# MSE450_G05_ASTEROIDS.net
KiCad netlist of a schematic drawn in Altium Designer
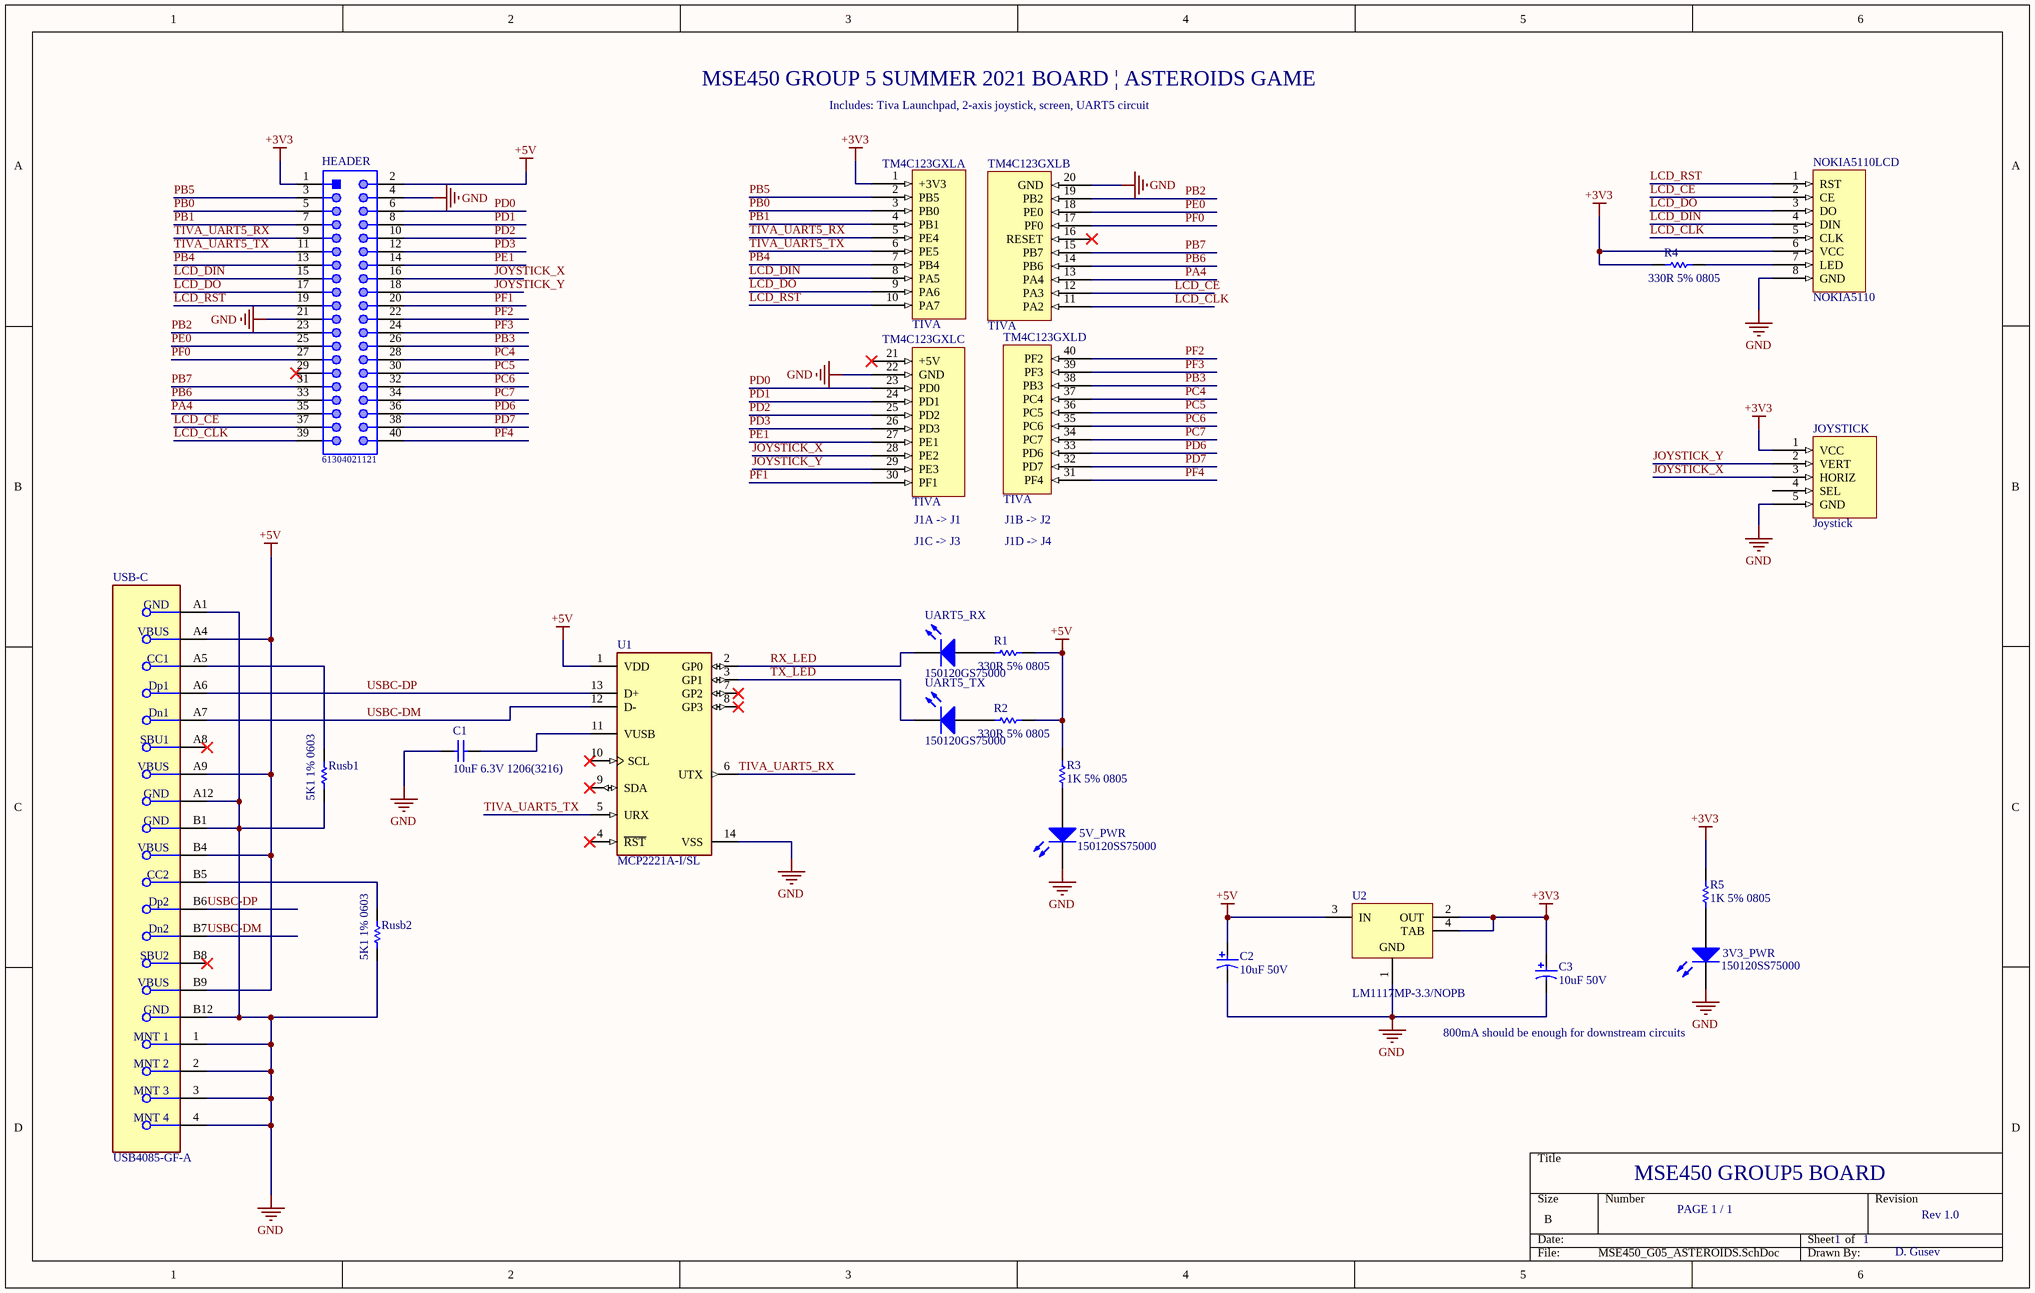
[diagram p0: MSE450_G05_ASTEROIDS.SchDoc]

(export (version "E")
  (design (tool "Eeschema 10.0.6"))
  (components
    (comp (ref "3V3_PWR")
      (value "150120SS75000")
      (footprint "1206_A")
      (description "SMD mono-color Chip LED, WL-SMCW, Super Red")
      (fields (field (name "MANUFACTURER") "Wuerth Elektronik"))
      (libsource (lib "Altium Content Vault") (part "WE-LED_K1A2-2"))
    )
    (comp (ref "5V_PWR")
      (value "150120SS75000")
      (footprint "1206_A")
      (description "SMD mono-color Chip LED, WL-SMCW, Super Red")
      (fields (field (name "MANUFACTURER") "Wuerth Elektronik"))
      (libsource (lib "Altium Content Vault") (part "WE-LED_K1A2-2"))
    )
    (comp (ref "C1")
      (value "10uF 6.3V 1206(3216)")
      (footprint "CAPC1206(3216)190_N")
      (description "CAP 10uF 6.3V ±10% 1206 (3216 Metric) Thickness 1.9mm SMD")
      (fields (field (name "TOLERANCE") "Â±10%"))
      (libsource (lib "Altium Content Vault") (part "CAP"))
    )
    (comp (ref "C2")
      (value "10uF 50V")
      (footprint "PNSC-FK-V-D_V")
      (fields (field (name "MANUFACTURER") "Panasonic"))
      (libsource (lib "Altium Content Vault") (part "CAP-P-2"))
    )
    (comp (ref "C3")
      (value "10uF 50V")
      (footprint "PNSC-FK-V-D_V")
      (fields (field (name "MANUFACTURER") "Panasonic"))
      (libsource (lib "Altium Content Vault") (part "CAP-P-2"))
    )
    (comp (ref "HEADER")
      (value "61304021121")
      (footprint "61304021121")
      (description "THT Vertical Pin Header WR-PHD, Pitch 2.54 mm, Dual Row, 40 pins")
      (fields (field (name "MANUFACTURER") "Wurth Elektronik") (field (name "PUBLISHER") "WurthElektronik"))
      (libsource (lib "Altium Content Vault") (part "WE-CN-2P-M-R40"))
    )
    (comp (ref "JOYSTICK")
      (value "Joystick")
      (footprint "joystick")
      (libsource (lib "MSE450_G05_ASTEROIDS") (part "Joystick"))
    )
    (comp (ref "NOKIA5110LCD")
      (value "NOKIA5110")
      (footprint "NOKIA5110")
      (libsource (lib "MSE450_G05_ASTEROIDS") (part "NOKIA5110"))
    )
    (comp (ref "R1")
      (value "330R 5% 0805")
      (footprint "RESC2013X60X40ML20T25")
      (fields (field (name "PART NUMBER") "ERA6AEB123V") (field (name "MANUFACTURER") "Panasonic"))
      (libsource (lib "Altium Content Vault") (part "RES"))
    )
    (comp (ref "R2")
      (value "330R 5% 0805")
      (footprint "RESC2013X60X40ML20T25")
      (fields (field (name "PART NUMBER") "ERA6AEB123V") (field (name "MANUFACTURER") "Panasonic"))
      (libsource (lib "Altium Content Vault") (part "RES"))
    )
    (comp (ref "R3")
      (value "1K 5% 0805")
      (footprint "RESC2013X60X40ML20T25")
      (fields (field (name "PART NUMBER") "ERA6AEB123V") (field (name "MANUFACTURER") "Panasonic"))
      (libsource (lib "Altium Content Vault") (part "RES"))
    )
    (comp (ref "R4")
      (value "330R 5% 0805")
      (footprint "RESC2013X60X40ML20T25")
      (fields (field (name "PART NUMBER") "ERA6AEB123V") (field (name "MANUFACTURER") "Panasonic"))
      (libsource (lib "Altium Content Vault") (part "RES"))
    )
    (comp (ref "R5")
      (value "1K 5% 0805")
      (footprint "RESC2013X60X40ML20T25")
      (fields (field (name "PART NUMBER") "ERA6AEB123V") (field (name "MANUFACTURER") "Panasonic"))
      (libsource (lib "Altium Content Vault") (part "RES"))
    )
    (comp (ref "Rusb1")
      (value "5K1 1% 0603")
      (footprint "RESC1608X55X25ML10T15")
      (fields (field (name "MANUFACTURER") "Yageo") (field (name "PART NUMBER") "RC0603FR-075K1L"))
      (libsource (lib "Altium Content Vault") (part "RES"))
    )
    (comp (ref "Rusb2")
      (value "5K1 1% 0603")
      (footprint "RESC1608X55X25ML10T15")
      (fields (field (name "MANUFACTURER") "Yageo") (field (name "PART NUMBER") "RC0603FR-075K1L"))
      (libsource (lib "Altium Content Vault") (part "RES"))
    )
    (comp (ref "TM4C123GXL")
      (value "TIVA")
      (footprint "TIVA")
      (libsource (lib "MSE450_G05_ASTEROIDS") (part "TIVA"))
    )
    (comp (ref "U1")
      (value "MCP2221A-I/SL")
      (footprint "FP-C04-065-SL-MFG")
      (description "IC USB TO I2C/UART 14SOIC")
      (fields
        (field (name "OCTOPART") "https://octopart.com/mcp2221a-i%2Fsl-microchip-71704986")
        (field (name "MANUFACTURER") "Microchip")
      )
      (libsource (lib "Altium Content Vault") (part "1b53208594fde27bd45fc2fa1d78706"))
    )
    (comp (ref "U2")
      (value "LM1117MP-3.3/NOPB")
      (footprint "DCY0004A_L")
      (description "800mA Low-Dropout Linear Regulator, 4-pin SOT-223, Pb-Free")
      (fields (field (name "MANUFACTURER") "Texas Instruments"))
      (libsource (lib "Altium Content Vault") (part "PM-REG-LM1086-SOT4"))
    )
    (comp (ref "UART5_RX")
      (value "150120GS75000")
      (footprint "1206_A")
      (description "SMD mono-color Chip LED, WL-SMCW, Green")
      (fields (field (name "MANUFACTURER") "Wuerth Elektronik"))
      (libsource (lib "Altium Content Vault") (part "WE-LED_K1A2-2"))
    )
    (comp (ref "UART5_TX")
      (value "150120GS75000")
      (footprint "1206_A")
      (description "SMD mono-color Chip LED, WL-SMCW, Green")
      (fields (field (name "MANUFACTURER") "Wuerth Elektronik"))
      (libsource (lib "Altium Content Vault") (part "WE-LED_K1A2-2"))
    )
    (comp (ref "USB-C")
      (value "USB4085-GF-A")
      (footprint "FP-USB4085-GF-A-MFG")
      (description "CONN RCPT USB2.0 TYPEC 16POS")
      (fields
        (field (name "MANUFACTURER") "Global Connector Technology")
        (field (name "OCTOPART") "https://octopart.com/usb4085-gf-a-global+connector+technology-94773699")
      )
      (libsource (lib "Altium Content Vault") (part "f6997dba88850a18107ac0013977506"))
    )
  )
  (nets
    (net (code "1") (name "+3V3") (class "Default")
      (node (ref "C3") (pin "1") (pinfunction "1_1") (pintype "passive"))
      (node (ref "HEADER") (pin "1") (pinfunction "1_1") (pintype "passive"))
      (node (ref "JOYSTICK") (pin "1") (pinfunction "VCC_1") (pintype "input"))
      (node (ref "NOKIA5110LCD") (pin "6") (pinfunction "VCC_6") (pintype "input"))
      (node (ref "R4") (pin "2") (pinfunction "2_2") (pintype "passive"))
      (node (ref "R5") (pin "1") (pinfunction "1_1") (pintype "passive"))
      (node (ref "TM4C123GXL") (pin "1") (pinfunction "+3V3_1") (pintype "input"))
      (node (ref "U2") (pin "2") (pinfunction "OUT_2") (pintype "power_in"))
      (node (ref "U2") (pin "4") (pinfunction "TAB_4") (pintype "power_in"))
    )
    (net (code "2") (name "+5V") (class "Default")
      (node (ref "C2") (pin "1") (pinfunction "1_1") (pintype "passive"))
      (node (ref "HEADER") (pin "2") (pinfunction "2_2") (pintype "passive"))
      (node (ref "R1") (pin "1") (pinfunction "1_1") (pintype "passive"))
      (node (ref "R2") (pin "1") (pinfunction "1_1") (pintype "passive"))
      (node (ref "R3") (pin "1") (pinfunction "1_1") (pintype "passive"))
      (node (ref "U1") (pin "1") (pinfunction "VDD_1") (pintype "power_in"))
      (node (ref "U2") (pin "3") (pinfunction "IN_3") (pintype "power_in"))
      (node (ref "USB-C") (pin "A4") (pinfunction "VBUS_A4") (pintype "power_in"))
      (node (ref "USB-C") (pin "A9") (pinfunction "VBUS_A9") (pintype "power_in"))
      (node (ref "USB-C") (pin "B4") (pinfunction "VBUS_B4") (pintype "power_in"))
      (node (ref "USB-C") (pin "B9") (pinfunction "VBUS_B9") (pintype "power_in"))
    )
    (net (code "3") (name "/JOYSTICK_X") (class "Default")
      (node (ref "HEADER") (pin "16") (pinfunction "16_16") (pintype "passive"))
      (node (ref "JOYSTICK") (pin "3") (pinfunction "HORIZ_3") (pintype "input"))
      (node (ref "TM4C123GXL") (pin "28") (pinfunction "PE2_28") (pintype "input"))
    )
    (net (code "4") (name "/JOYSTICK_Y") (class "Default")
      (node (ref "HEADER") (pin "18") (pinfunction "18_18") (pintype "passive"))
      (node (ref "JOYSTICK") (pin "2") (pinfunction "VERT_2") (pintype "input"))
      (node (ref "TM4C123GXL") (pin "29") (pinfunction "PE3_29") (pintype "input"))
    )
    (net (code "5") (name "/LCD_CE") (class "Default")
      (node (ref "HEADER") (pin "37") (pinfunction "37_37") (pintype "passive"))
      (node (ref "NOKIA5110LCD") (pin "2") (pinfunction "CE_2") (pintype "input"))
      (node (ref "TM4C123GXL") (pin "12") (pinfunction "PA3_12") (pintype "input"))
    )
    (net (code "6") (name "/LCD_CLK") (class "Default")
      (node (ref "HEADER") (pin "39") (pinfunction "39_39") (pintype "passive"))
      (node (ref "NOKIA5110LCD") (pin "5") (pinfunction "CLK_5") (pintype "input"))
      (node (ref "TM4C123GXL") (pin "11") (pinfunction "PA2_11") (pintype "input"))
    )
    (net (code "7") (name "/LCD_DIN") (class "Default")
      (node (ref "HEADER") (pin "15") (pinfunction "15_15") (pintype "passive"))
      (node (ref "NOKIA5110LCD") (pin "4") (pinfunction "DIN_4") (pintype "input"))
      (node (ref "TM4C123GXL") (pin "8") (pinfunction "PA5_8") (pintype "input"))
    )
    (net (code "8") (name "/LCD_DO") (class "Default")
      (node (ref "HEADER") (pin "17") (pinfunction "17_17") (pintype "passive"))
      (node (ref "NOKIA5110LCD") (pin "3") (pinfunction "DO_3") (pintype "input"))
      (node (ref "TM4C123GXL") (pin "9") (pinfunction "PA6_9") (pintype "input"))
    )
    (net (code "9") (name "/LCD_RST") (class "Default")
      (node (ref "HEADER") (pin "19") (pinfunction "19_19") (pintype "passive"))
      (node (ref "NOKIA5110LCD") (pin "1") (pinfunction "RST_1") (pintype "input"))
      (node (ref "TM4C123GXL") (pin "10") (pinfunction "PA7_10") (pintype "input"))
    )
    (net (code "10") (name "/PA4") (class "Default")
      (node (ref "HEADER") (pin "35") (pinfunction "35_35") (pintype "passive"))
      (node (ref "TM4C123GXL") (pin "13") (pinfunction "PA4_13") (pintype "input"))
    )
    (net (code "11") (name "/PB0") (class "Default")
      (node (ref "HEADER") (pin "5") (pinfunction "5_5") (pintype "passive"))
      (node (ref "TM4C123GXL") (pin "3") (pinfunction "PB0_3") (pintype "input"))
    )
    (net (code "12") (name "/PB1") (class "Default")
      (node (ref "HEADER") (pin "7") (pinfunction "7_7") (pintype "passive"))
      (node (ref "TM4C123GXL") (pin "4") (pinfunction "PB1_4") (pintype "input"))
    )
    (net (code "13") (name "/PB2") (class "Default")
      (node (ref "HEADER") (pin "23") (pinfunction "23_23") (pintype "passive"))
      (node (ref "TM4C123GXL") (pin "19") (pinfunction "PB2_19") (pintype "input"))
    )
    (net (code "14") (name "/PB3") (class "Default")
      (node (ref "HEADER") (pin "26") (pinfunction "26_26") (pintype "passive"))
      (node (ref "TM4C123GXL") (pin "38") (pinfunction "PB3_38") (pintype "input"))
    )
    (net (code "15") (name "/PB4") (class "Default")
      (node (ref "HEADER") (pin "13") (pinfunction "13_13") (pintype "passive"))
      (node (ref "TM4C123GXL") (pin "7") (pinfunction "PB4_7") (pintype "input"))
    )
    (net (code "16") (name "/PB5") (class "Default")
      (node (ref "HEADER") (pin "3") (pinfunction "3_3") (pintype "passive"))
      (node (ref "TM4C123GXL") (pin "2") (pinfunction "PB5_2") (pintype "input"))
    )
    (net (code "17") (name "/PB6") (class "Default")
      (node (ref "HEADER") (pin "33") (pinfunction "33_33") (pintype "passive"))
      (node (ref "TM4C123GXL") (pin "14") (pinfunction "PB6_14") (pintype "input"))
    )
    (net (code "18") (name "/PB7") (class "Default")
      (node (ref "HEADER") (pin "31") (pinfunction "31_31") (pintype "passive"))
      (node (ref "TM4C123GXL") (pin "15") (pinfunction "PB7_15") (pintype "input"))
    )
    (net (code "19") (name "/PC4") (class "Default")
      (node (ref "HEADER") (pin "28") (pinfunction "28_28") (pintype "passive"))
      (node (ref "TM4C123GXL") (pin "37") (pinfunction "PC4_37") (pintype "input"))
    )
    (net (code "20") (name "/PC5") (class "Default")
      (node (ref "HEADER") (pin "30") (pinfunction "30_30") (pintype "passive"))
      (node (ref "TM4C123GXL") (pin "36") (pinfunction "PC5_36") (pintype "input"))
    )
    (net (code "21") (name "/PC6") (class "Default")
      (node (ref "HEADER") (pin "32") (pinfunction "32_32") (pintype "passive"))
      (node (ref "TM4C123GXL") (pin "35") (pinfunction "PC6_35") (pintype "input"))
    )
    (net (code "22") (name "/PC7") (class "Default")
      (node (ref "HEADER") (pin "34") (pinfunction "34_34") (pintype "passive"))
      (node (ref "TM4C123GXL") (pin "34") (pinfunction "PC7_34") (pintype "input"))
    )
    (net (code "23") (name "/PD0") (class "Default")
      (node (ref "HEADER") (pin "6") (pinfunction "6_6") (pintype "passive"))
      (node (ref "TM4C123GXL") (pin "23") (pinfunction "PD0_23") (pintype "input"))
    )
    (net (code "24") (name "/PD1") (class "Default")
      (node (ref "HEADER") (pin "8") (pinfunction "8_8") (pintype "passive"))
      (node (ref "TM4C123GXL") (pin "24") (pinfunction "PD1_24") (pintype "input"))
    )
    (net (code "25") (name "/PD2") (class "Default")
      (node (ref "HEADER") (pin "10") (pinfunction "10_10") (pintype "passive"))
      (node (ref "TM4C123GXL") (pin "25") (pinfunction "PD2_25") (pintype "input"))
    )
    (net (code "26") (name "/PD3") (class "Default")
      (node (ref "HEADER") (pin "12") (pinfunction "12_12") (pintype "passive"))
      (node (ref "TM4C123GXL") (pin "26") (pinfunction "PD3_26") (pintype "input"))
    )
    (net (code "27") (name "/PD6") (class "Default")
      (node (ref "HEADER") (pin "36") (pinfunction "36_36") (pintype "passive"))
      (node (ref "TM4C123GXL") (pin "33") (pinfunction "PD6_33") (pintype "input"))
    )
    (net (code "28") (name "/PD7") (class "Default")
      (node (ref "HEADER") (pin "38") (pinfunction "38_38") (pintype "passive"))
      (node (ref "TM4C123GXL") (pin "32") (pinfunction "PD7_32") (pintype "input"))
    )
    (net (code "29") (name "/PE0") (class "Default")
      (node (ref "HEADER") (pin "25") (pinfunction "25_25") (pintype "passive"))
      (node (ref "TM4C123GXL") (pin "18") (pinfunction "PE0_18") (pintype "input"))
    )
    (net (code "30") (name "/PE1") (class "Default")
      (node (ref "HEADER") (pin "14") (pinfunction "14_14") (pintype "passive"))
      (node (ref "TM4C123GXL") (pin "27") (pinfunction "PE1_27") (pintype "input"))
    )
    (net (code "31") (name "/PF0") (class "Default")
      (node (ref "HEADER") (pin "27") (pinfunction "27_27") (pintype "passive"))
      (node (ref "TM4C123GXL") (pin "17") (pinfunction "PF0_17") (pintype "input"))
    )
    (net (code "32") (name "/PF1") (class "Default")
      (node (ref "HEADER") (pin "20") (pinfunction "20_20") (pintype "passive"))
      (node (ref "TM4C123GXL") (pin "30") (pinfunction "PF1_30") (pintype "input"))
    )
    (net (code "33") (name "/PF2") (class "Default")
      (node (ref "HEADER") (pin "22") (pinfunction "22_22") (pintype "passive"))
      (node (ref "TM4C123GXL") (pin "40") (pinfunction "PF2_40") (pintype "input"))
    )
    (net (code "34") (name "/PF3") (class "Default")
      (node (ref "HEADER") (pin "24") (pinfunction "24_24") (pintype "passive"))
      (node (ref "TM4C123GXL") (pin "39") (pinfunction "PF3_39") (pintype "input"))
    )
    (net (code "35") (name "/PF4") (class "Default")
      (node (ref "HEADER") (pin "40") (pinfunction "40_40") (pintype "passive"))
      (node (ref "TM4C123GXL") (pin "31") (pinfunction "PF4_31") (pintype "input"))
    )
    (net (code "36") (name "/RX_LED") (class "Default")
      (node (ref "U1") (pin "2") (pinfunction "GP0_2") (pintype "bidirectional"))
      (node (ref "UART5_RX") (pin "1") (pinfunction "K_1") (pintype "passive"))
    )
    (net (code "37") (name "/TIVA_UART5_RX") (class "Default")
      (node (ref "HEADER") (pin "9") (pinfunction "9_9") (pintype "passive"))
      (node (ref "TM4C123GXL") (pin "5") (pinfunction "PE4_5") (pintype "input"))
      (node (ref "U1") (pin "6") (pinfunction "UTX_6") (pintype "output"))
    )
    (net (code "38") (name "/TIVA_UART5_TX") (class "Default")
      (node (ref "HEADER") (pin "11") (pinfunction "11_11") (pintype "passive"))
      (node (ref "TM4C123GXL") (pin "6") (pinfunction "PE5_6") (pintype "input"))
      (node (ref "U1") (pin "5") (pinfunction "URX_5") (pintype "input"))
    )
    (net (code "39") (name "/TX_LED") (class "Default")
      (node (ref "U1") (pin "3") (pinfunction "GP1_3") (pintype "bidirectional"))
      (node (ref "UART5_TX") (pin "1") (pinfunction "K_1") (pintype "passive"))
    )
    (net (code "40") (name "/USBC-DM") (class "Default")
      (node (ref "U1") (pin "12") (pinfunction "D-_12") (pintype "power_in"))
      (node (ref "USB-C") (pin "A7") (pinfunction "Dn1_A7") (pintype "passive"))
      (node (ref "USB-C") (pin "B7") (pinfunction "Dn2_B7") (pintype "passive"))
    )
    (net (code "41") (name "/USBC-DP") (class "Default")
      (node (ref "U1") (pin "13") (pinfunction "D+_13") (pintype "power_in"))
      (node (ref "USB-C") (pin "A6") (pinfunction "Dp1_A6") (pintype "passive"))
      (node (ref "USB-C") (pin "B6") (pinfunction "Dp2_B6") (pintype "passive"))
    )
    (net (code "42") (name "GND") (class "Default")
      (node (ref "3V3_PWR") (pin "1") (pinfunction "K_1") (pintype "passive"))
      (node (ref "5V_PWR") (pin "1") (pinfunction "K_1") (pintype "passive"))
      (node (ref "C1") (pin "1") (pinfunction "1_1") (pintype "passive"))
      (node (ref "C2") (pin "2") (pinfunction "2_2") (pintype "passive"))
      (node (ref "C3") (pin "2") (pinfunction "2_2") (pintype "passive"))
      (node (ref "HEADER") (pin "21") (pinfunction "21_21") (pintype "passive"))
      (node (ref "HEADER") (pin "4") (pinfunction "4_4") (pintype "passive"))
      (node (ref "JOYSTICK") (pin "5") (pinfunction "GND_5") (pintype "input"))
      (node (ref "NOKIA5110LCD") (pin "8") (pinfunction "GND_8") (pintype "input"))
      (node (ref "Rusb1") (pin "1") (pinfunction "1_1") (pintype "passive"))
      (node (ref "Rusb2") (pin "1") (pinfunction "1_1") (pintype "passive"))
      (node (ref "TM4C123GXL") (pin "20") (pinfunction "GND_20") (pintype "input"))
      (node (ref "TM4C123GXL") (pin "22") (pinfunction "GND_22") (pintype "input"))
      (node (ref "U1") (pin "14") (pinfunction "VSS_14") (pintype "power_in"))
      (node (ref "U2") (pin "1") (pinfunction "GND_1") (pintype "power_in"))
      (node (ref "USB-C") (pin "1") (pinfunction "MNT_1_1") (pintype "passive"))
      (node (ref "USB-C") (pin "2") (pinfunction "MNT_2_2") (pintype "passive"))
      (node (ref "USB-C") (pin "3") (pinfunction "MNT_3_3") (pintype "passive"))
      (node (ref "USB-C") (pin "4") (pinfunction "MNT_4_4") (pintype "passive"))
      (node (ref "USB-C") (pin "A1") (pinfunction "GND_A1") (pintype "power_in"))
      (node (ref "USB-C") (pin "A12") (pinfunction "GND_A12") (pintype "power_in"))
      (node (ref "USB-C") (pin "B1") (pinfunction "GND_B1") (pintype "power_in"))
      (node (ref "USB-C") (pin "B12") (pinfunction "GND_B12") (pintype "power_in"))
    )
    (net (code "43") (name "Net-(3V3_PWR-A)") (class "Default")
      (node (ref "3V3_PWR") (pin "2") (pinfunction "A_2") (pintype "passive"))
      (node (ref "R5") (pin "2") (pinfunction "2_2") (pintype "passive"))
    )
    (net (code "44") (name "Net-(5V_PWR-A)") (class "Default")
      (node (ref "5V_PWR") (pin "2") (pinfunction "A_2") (pintype "passive"))
      (node (ref "R3") (pin "2") (pinfunction "2_2") (pintype "passive"))
    )
    (net (code "45") (name "Net-(NOKIA5110LCD-LED)") (class "Default")
      (node (ref "NOKIA5110LCD") (pin "7") (pinfunction "LED_7") (pintype "input"))
      (node (ref "R4") (pin "1") (pinfunction "1_1") (pintype "passive"))
    )
    (net (code "46") (name "Net-(U1-VUSB)") (class "Default")
      (node (ref "C1") (pin "2") (pinfunction "2_2") (pintype "passive"))
      (node (ref "U1") (pin "11") (pinfunction "VUSB_11") (pintype "power_in"))
    )
    (net (code "47") (name "Net-(UART5_RX-A)") (class "Default")
      (node (ref "R1") (pin "2") (pinfunction "2_2") (pintype "passive"))
      (node (ref "UART5_RX") (pin "2") (pinfunction "A_2") (pintype "passive"))
    )
    (net (code "48") (name "Net-(UART5_TX-A)") (class "Default")
      (node (ref "R2") (pin "2") (pinfunction "2_2") (pintype "passive"))
      (node (ref "UART5_TX") (pin "2") (pinfunction "A_2") (pintype "passive"))
    )
    (net (code "49") (name "Net-(USB-C-CC1)") (class "Default")
      (node (ref "Rusb1") (pin "2") (pinfunction "2_2") (pintype "passive"))
      (node (ref "USB-C") (pin "A5") (pinfunction "CC1_A5") (pintype "passive"))
    )
    (net (code "50") (name "Net-(USB-C-CC2)") (class "Default")
      (node (ref "Rusb2") (pin "2") (pinfunction "2_2") (pintype "passive"))
      (node (ref "USB-C") (pin "B5") (pinfunction "CC2_B5") (pintype "passive"))
    )
    (net (code "51") (name "unconnected-(HEADER-Pad29)") (class "Default")
      (node (ref "HEADER") (pin "29") (pinfunction "29_29") (pintype "passive+no_connect"))
    )
    (net (code "52") (name "unconnected-(JOYSTICK-SEL-Pad4)") (class "Default")
      (node (ref "JOYSTICK") (pin "4") (pinfunction "SEL_4") (pintype "input"))
    )
    (net (code "53") (name "unconnected-(TM4C123GXLB-RESET-Pad16)") (class "Default")
      (node (ref "TM4C123GXL") (pin "16") (pinfunction "RESET_16") (pintype "input+no_connect"))
    )
    (net (code "54") (name "unconnected-(TM4C123GXLC-+5V-Pad21)") (class "Default")
      (node (ref "TM4C123GXL") (pin "21") (pinfunction "+5V_21") (pintype "input+no_connect"))
    )
    (net (code "55") (name "unconnected-(U1-GP2-Pad7)") (class "Default")
      (node (ref "U1") (pin "7") (pinfunction "GP2_7") (pintype "bidirectional+no_connect"))
    )
    (net (code "56") (name "unconnected-(U1-GP3-Pad8)") (class "Default")
      (node (ref "U1") (pin "8") (pinfunction "GP3_8") (pintype "bidirectional+no_connect"))
    )
    (net (code "57") (name "unconnected-(U1-SCL-Pad10)") (class "Default")
      (node (ref "U1") (pin "10") (pinfunction "SCL_10") (pintype "input+no_connect"))
    )
    (net (code "58") (name "unconnected-(U1-SDA-Pad9)") (class "Default")
      (node (ref "U1") (pin "9") (pinfunction "SDA_9") (pintype "bidirectional+no_connect"))
    )
    (net (code "59") (name "unconnected-(U1-~{RST}-Pad4)") (class "Default")
      (node (ref "U1") (pin "4") (pinfunction "~{RST}_4") (pintype "input+no_connect"))
    )
    (net (code "60") (name "unconnected-(USB-C-SBU1-PadA8)") (class "Default")
      (node (ref "USB-C") (pin "A8") (pinfunction "SBU1_A8") (pintype "passive+no_connect"))
    )
    (net (code "61") (name "unconnected-(USB-C-SBU2-PadB8)") (class "Default")
      (node (ref "USB-C") (pin "B8") (pinfunction "SBU2_B8") (pintype "passive+no_connect"))
    )
  )
)
